# untitled.net
KiCad netlist of a schematic drawn in EAGLE
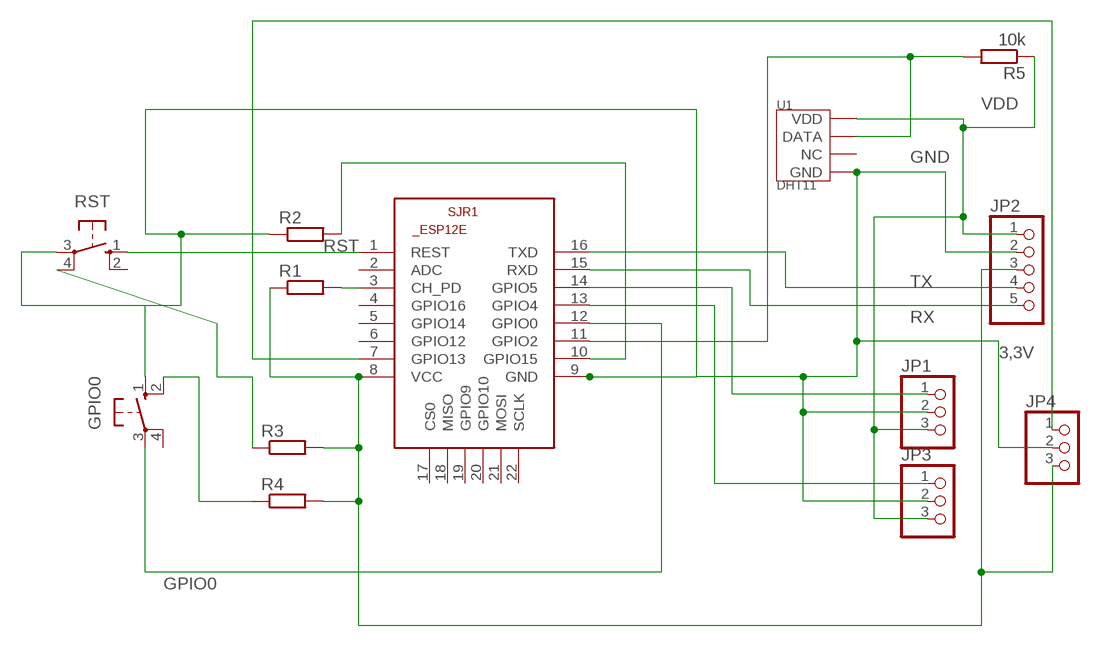
[diagram p0: schematic, sheet 1]

(export (version "E")
  (design (tool "Eeschema 10.0.6"))
  (components
    (comp (ref "GPIO0")
      (value "10-XX")
      (footprint "eagle-import:B3F-10XX")
      (fields (field (name "MPN") "B3F-1000"))
      (libsource (lib "eagle-import") (part "10-XX"))
    )
    (comp (ref "JP1")
      (value "PINHD-1X3")
      (footprint "eagle-import:1X03")
      (libsource (lib "eagle-import") (part "PINHD-1X3"))
    )
    (comp (ref "JP2")
      (value "PINHD-1X5")
      (footprint "eagle-import:1X05")
      (libsource (lib "eagle-import") (part "PINHD-1X5"))
    )
    (comp (ref "JP3")
      (value "PINHD-1X3")
      (footprint "eagle-import:1X03")
      (libsource (lib "eagle-import") (part "PINHD-1X3"))
    )
    (comp (ref "JP4")
      (value "PINHD-1X3")
      (footprint "eagle-import:1X03")
      (libsource (lib "eagle-import") (part "PINHD-1X3"))
    )
    (comp (ref "R1")
      (value "R-EU_0207/10")
      (footprint "eagle-import:0207_10")
      (libsource (lib "eagle-import") (part "R-EU_0207/10"))
    )
    (comp (ref "R2")
      (value "R-EU_0207/10")
      (footprint "eagle-import:0207_10")
      (libsource (lib "eagle-import") (part "R-EU_0207/10"))
    )
    (comp (ref "R3")
      (value "R-EU_0207/10")
      (footprint "eagle-import:0207_10")
      (libsource (lib "eagle-import") (part "R-EU_0207/10"))
    )
    (comp (ref "R4")
      (value "R-EU_0207/10")
      (footprint "eagle-import:0207_10")
      (libsource (lib "eagle-import") (part "R-EU_0207/10"))
    )
    (comp (ref "R5")
      (value "10k")
      (footprint "eagle-import:0207_10")
      (libsource (lib "eagle-import") (part "R-EU_0207/10"))
    )
    (comp (ref "RST")
      (value "10-XX")
      (footprint "eagle-import:B3F-10XX")
      (fields (field (name "MPN") "B3F-1000"))
      (libsource (lib "eagle-import") (part "10-XX"))
    )
    (comp (ref "SJR1")
      (value "ESP8266-12EESP12E")
      (footprint "eagle-import:ESP8266-ESP12E")
      (libsource (lib "eagle-import") (part "ESP8266-12EESP12E"))
    )
    (comp (ref "U1")
      (value "DHT11")
      (footprint "eagle-import:SNR4-2.54-15.5X12.0X5.5MM")
      (libsource (lib "eagle-import") (part "TEM-HUM-DHT11(4P-15.5X12.0MM)"))
    )
  )
  (nets
    (net (code "1") (name "/3,3V") (class "Default")
      (node (ref "JP2") (pin "3") (pinfunction "3_3") (pintype "passive"))
      (node (ref "JP4") (pin "3") (pinfunction "3_3") (pintype "passive"))
      (node (ref "R1") (pin "1") (pinfunction "1_1") (pintype "passive"))
      (node (ref "R3") (pin "2") (pinfunction "2_2") (pintype "passive"))
      (node (ref "R4") (pin "2") (pinfunction "2_2") (pintype "passive"))
      (node (ref "SJR1") (pin "8") (pinfunction "VCC_8") (pintype "bidirectional"))
    )
    (net (code "2") (name "/GND") (class "Default")
      (node (ref "GPIO0") (pin "1") (pinfunction "S_1") (pintype "passive"))
      (node (ref "JP1") (pin "2") (pinfunction "2_2") (pintype "passive"))
      (node (ref "JP2") (pin "2") (pinfunction "2_2") (pintype "passive"))
      (node (ref "JP3") (pin "2") (pinfunction "2_2") (pintype "passive"))
      (node (ref "JP4") (pin "2") (pinfunction "2_2") (pintype "passive"))
      (node (ref "R2") (pin "1") (pinfunction "1_1") (pintype "passive"))
      (node (ref "RST") (pin "3") (pinfunction "P_3") (pintype "passive"))
      (node (ref "SJR1") (pin "9") (pinfunction "GND_9") (pintype "bidirectional"))
      (node (ref "U1") (pin "4") (pinfunction "GND_4") (pintype "power_in"))
    )
    (net (code "3") (name "/GPIO0") (class "Default")
      (node (ref "GPIO0") (pin "3") (pinfunction "P_3") (pintype "passive"))
      (node (ref "SJR1") (pin "12") (pinfunction "GPIO0_12") (pintype "bidirectional"))
    )
    (net (code "4") (name "/RST") (class "Default")
      (node (ref "RST") (pin "1") (pinfunction "S_1") (pintype "passive"))
      (node (ref "SJR1") (pin "1") (pinfunction "REST_1") (pintype "bidirectional"))
    )
    (net (code "5") (name "/RX") (class "Default")
      (node (ref "JP2") (pin "5") (pinfunction "5_5") (pintype "passive"))
      (node (ref "SJR1") (pin "15") (pinfunction "RXD_15") (pintype "bidirectional"))
    )
    (net (code "6") (name "/TX") (class "Default")
      (node (ref "JP2") (pin "4") (pinfunction "4_4") (pintype "passive"))
      (node (ref "SJR1") (pin "16") (pinfunction "TXD_16") (pintype "bidirectional"))
    )
    (net (code "7") (name "/VDD") (class "Default")
      (node (ref "JP1") (pin "3") (pinfunction "3_3") (pintype "passive"))
      (node (ref "JP2") (pin "1") (pinfunction "1_1") (pintype "passive"))
      (node (ref "JP3") (pin "3") (pinfunction "3_3") (pintype "passive"))
      (node (ref "R5") (pin "1") (pinfunction "1_1") (pintype "passive"))
      (node (ref "U1") (pin "1") (pinfunction "VDD_1") (pintype "power_in"))
    )
    (net (code "8") (name "Net-(GPIO0-S1)") (class "Default")
      (node (ref "GPIO0") (pin "2") (pinfunction "S1_2") (pintype "passive"))
      (node (ref "R4") (pin "1") (pinfunction "1_1") (pintype "passive"))
    )
    (net (code "9") (name "Net-(RST-P1)") (class "Default")
      (node (ref "R3") (pin "1") (pinfunction "1_1") (pintype "passive"))
      (node (ref "RST") (pin "4") (pinfunction "P1_4") (pintype "passive"))
    )
    (net (code "10") (name "Net-(SJR1-CH_PD)") (class "Default")
      (node (ref "R1") (pin "2") (pinfunction "2_2") (pintype "passive"))
      (node (ref "SJR1") (pin "3") (pinfunction "CH_PD_3") (pintype "bidirectional"))
    )
    (net (code "11") (name "Net-(SJR1-GPIO2)") (class "Default")
      (node (ref "R5") (pin "2") (pinfunction "2_2") (pintype "passive"))
      (node (ref "SJR1") (pin "11") (pinfunction "GPIO2_11") (pintype "bidirectional"))
      (node (ref "U1") (pin "2") (pinfunction "DATA_2") (pintype "bidirectional"))
    )
    (net (code "12") (name "Net-(SJR1-GPIO4)") (class "Default")
      (node (ref "JP3") (pin "1") (pinfunction "1_1") (pintype "passive"))
      (node (ref "SJR1") (pin "13") (pinfunction "GPIO4_13") (pintype "bidirectional"))
    )
    (net (code "13") (name "Net-(SJR1-GPIO5)") (class "Default")
      (node (ref "JP1") (pin "1") (pinfunction "1_1") (pintype "passive"))
      (node (ref "SJR1") (pin "14") (pinfunction "GPIO5_14") (pintype "bidirectional"))
    )
    (net (code "14") (name "Net-(SJR1-GPIO13)") (class "Default")
      (node (ref "JP4") (pin "1") (pinfunction "1_1") (pintype "passive"))
      (node (ref "SJR1") (pin "7") (pinfunction "GPIO13_7") (pintype "bidirectional"))
    )
    (net (code "15") (name "Net-(SJR1-GPIO15)") (class "Default")
      (node (ref "R2") (pin "2") (pinfunction "2_2") (pintype "passive"))
      (node (ref "SJR1") (pin "10") (pinfunction "GPIO15_10") (pintype "bidirectional"))
    )
    (net (code "16") (name "unconnected-(GPIO0-P1-Pad4)") (class "Default")
      (node (ref "GPIO0") (pin "4") (pinfunction "P1_4") (pintype "passive"))
    )
    (net (code "17") (name "unconnected-(RST-S1-Pad2)") (class "Default")
      (node (ref "RST") (pin "2") (pinfunction "S1_2") (pintype "passive"))
    )
    (net (code "18") (name "unconnected-(SJR1-ADC-Pad2)") (class "Default")
      (node (ref "SJR1") (pin "2") (pinfunction "ADC_2") (pintype "bidirectional"))
    )
    (net (code "19") (name "unconnected-(SJR1-CS0-Pad17)") (class "Default")
      (node (ref "SJR1") (pin "17") (pinfunction "CS0_17") (pintype "bidirectional"))
    )
    (net (code "20") (name "unconnected-(SJR1-GPIO9-Pad19)") (class "Default")
      (node (ref "SJR1") (pin "19") (pinfunction "GPIO9_19") (pintype "bidirectional"))
    )
    (net (code "21") (name "unconnected-(SJR1-GPIO10-Pad20)") (class "Default")
      (node (ref "SJR1") (pin "20") (pinfunction "GPIO10_20") (pintype "bidirectional"))
    )
    (net (code "22") (name "unconnected-(SJR1-GPIO12-Pad6)") (class "Default")
      (node (ref "SJR1") (pin "6") (pinfunction "GPIO12_6") (pintype "bidirectional"))
    )
    (net (code "23") (name "unconnected-(SJR1-GPIO14-Pad5)") (class "Default")
      (node (ref "SJR1") (pin "5") (pinfunction "GPIO14_5") (pintype "bidirectional"))
    )
    (net (code "24") (name "unconnected-(SJR1-GPIO16-Pad4)") (class "Default")
      (node (ref "SJR1") (pin "4") (pinfunction "GPIO16_4") (pintype "bidirectional"))
    )
    (net (code "25") (name "unconnected-(SJR1-MISO-Pad18)") (class "Default")
      (node (ref "SJR1") (pin "18") (pinfunction "MISO_18") (pintype "bidirectional"))
    )
    (net (code "26") (name "unconnected-(SJR1-MOSI-Pad21)") (class "Default")
      (node (ref "SJR1") (pin "21") (pinfunction "MOSI_21") (pintype "bidirectional"))
    )
    (net (code "27") (name "unconnected-(SJR1-SCLK-Pad22)") (class "Default")
      (node (ref "SJR1") (pin "22") (pinfunction "SCLK_22") (pintype "bidirectional"))
    )
    (net (code "28") (name "unconnected-(U1-NC-Pad3)") (class "Default")
      (node (ref "U1") (pin "3") (pinfunction "NC_3") (pintype "no_connect"))
    )
  )
)
